# zoetrope.net
KiCad netlist of a schematic drawn in EAGLE
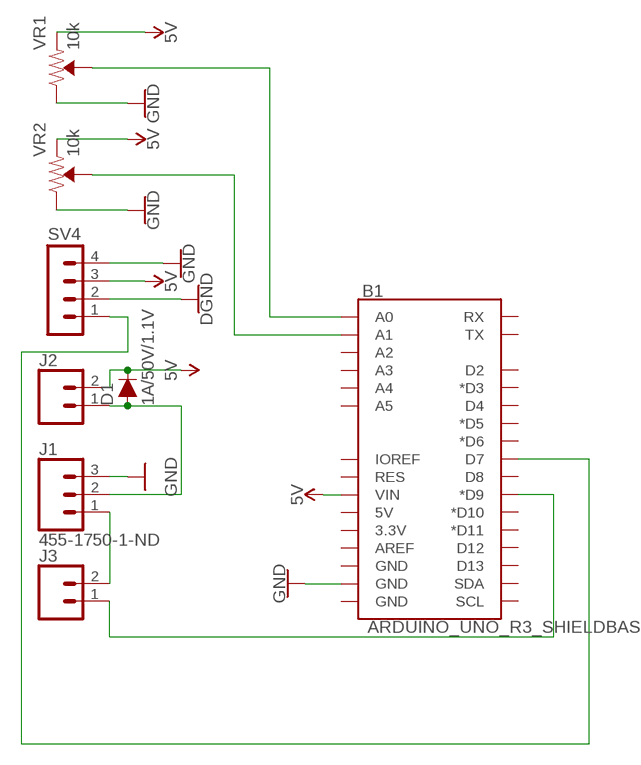
[diagram p0: schematic, sheet 1]

(export (version "E")
  (design (tool "Eeschema 10.0.6"))
  (components
    (comp (ref "B1")
      (value "ARDUINO_UNO_R3_SHIELDBASIC")
      (footprint "eagle-import:UNO_R3_SHIELD")
      (libsource (lib "eagle-import") (part "ARDUINO_UNO_R3_SHIELDBASIC"))
    )
    (comp (ref "D1")
      (value "1A/50V/1.1V")
      (footprint "eagle-import:DIODE-1N4001")
      (libsource (lib "eagle-import") (part "DIODE-PTH"))
    )
    (comp (ref "J1")
      (value "455-1750-1-ND")
      (footprint "eagle-import:1X03")
      (libsource (lib "eagle-import") (part "CONN_03"))
    )
    (comp (ref "J2")
      (value "CONN_02")
      (footprint "eagle-import:1X02")
      (libsource (lib "eagle-import") (part "CONN_02"))
    )
    (comp (ref "J3")
      (value "CONN_02")
      (footprint "eagle-import:1X02")
      (libsource (lib "eagle-import") (part "CONN_02"))
    )
    (comp (ref "SV4")
      (value "MA04-1")
      (footprint "eagle-import:MA04-1")
      (libsource (lib "eagle-import") (part "MA04-1"))
    )
    (comp (ref "VR1")
      (value "10k")
      (footprint "eagle-import:TRIMPOT-PTH-3386U")
      (libsource (lib "eagle-import") (part "TRIMPOT-PTH-10MM-KNOB-1/2W-10%"))
    )
    (comp (ref "VR2")
      (value "10k")
      (footprint "eagle-import:TRIMPOT-PTH-3386U")
      (libsource (lib "eagle-import") (part "TRIMPOT-PTH-10MM-KNOB-1/2W-10%"))
    )
  )
  (nets
    (net (code "1") (name "5V") (class "Default")
      (node (ref "B1") (pin "VIN") (pinfunction "VIN_VIN") (pintype "bidirectional"))
      (node (ref "D1") (pin "C") (pinfunction "C_C") (pintype "passive"))
      (node (ref "J2") (pin "2") (pinfunction "2_2") (pintype "passive"))
      (node (ref "SV4") (pin "3") (pinfunction "3_3") (pintype "passive"))
      (node (ref "VR1") (pin "1") (pinfunction "CCW_1") (pintype "passive"))
      (node (ref "VR2") (pin "1") (pinfunction "CCW_1") (pintype "passive"))
    )
    (net (code "2") (name "DGND") (class "Default")
      (node (ref "B1") (pin "GND@1") (pinfunction "GND_GND@1") (pintype "bidirectional"))
      (node (ref "J1") (pin "3") (pinfunction "3_3") (pintype "passive"))
      (node (ref "SV4") (pin "2") (pinfunction "2_2") (pintype "passive"))
      (node (ref "SV4") (pin "4") (pinfunction "4_4") (pintype "passive"))
      (node (ref "VR1") (pin "3") (pinfunction "CW_3") (pintype "passive"))
      (node (ref "VR2") (pin "3") (pinfunction "CW_3") (pintype "passive"))
    )
    (net (code "3") (name "Net-(B1-*D9)") (class "Default")
      (node (ref "B1") (pin "D9") (pinfunction "*D9_D9") (pintype "bidirectional"))
      (node (ref "J3") (pin "1") (pinfunction "1_1") (pintype "passive"))
    )
    (net (code "4") (name "Net-(B1-PadD7)") (class "Default")
      (node (ref "B1") (pin "D7") (pinfunction "D7_D7") (pintype "bidirectional"))
      (node (ref "SV4") (pin "1") (pinfunction "1_1") (pintype "passive"))
    )
    (net (code "5") (name "Net-(D1-PadA)") (class "Default")
      (node (ref "D1") (pin "A") (pinfunction "A_A") (pintype "passive"))
      (node (ref "J1") (pin "2") (pinfunction "2_2") (pintype "passive"))
      (node (ref "J2") (pin "1") (pinfunction "1_1") (pintype "passive"))
    )
    (net (code "6") (name "Net-(J1-Pad1)") (class "Default")
      (node (ref "J1") (pin "1") (pinfunction "1_1") (pintype "passive"))
      (node (ref "J3") (pin "2") (pinfunction "2_2") (pintype "passive"))
    )
    (net (code "7") (name "Net-(VR1-WIPER)") (class "Default")
      (node (ref "B1") (pin "A0") (pinfunction "A0_A0") (pintype "bidirectional"))
      (node (ref "VR1") (pin "2") (pinfunction "WIPER_2") (pintype "passive"))
    )
    (net (code "8") (name "Net-(VR2-WIPER)") (class "Default")
      (node (ref "B1") (pin "A1") (pinfunction "A1_A1") (pintype "bidirectional"))
      (node (ref "VR2") (pin "2") (pinfunction "WIPER_2") (pintype "passive"))
    )
    (net (code "9") (name "unconnected-(B1-*D3-PadD3)") (class "Default")
      (node (ref "B1") (pin "D3") (pinfunction "*D3_D3") (pintype "bidirectional"))
    )
    (net (code "10") (name "unconnected-(B1-*D5-PadD5)") (class "Default")
      (node (ref "B1") (pin "D5") (pinfunction "*D5_D5") (pintype "bidirectional"))
    )
    (net (code "11") (name "unconnected-(B1-*D6-PadD6)") (class "Default")
      (node (ref "B1") (pin "D6") (pinfunction "*D6_D6") (pintype "bidirectional"))
    )
    (net (code "12") (name "unconnected-(B1-*D10-PadD10)") (class "Default")
      (node (ref "B1") (pin "D10") (pinfunction "*D10_D10") (pintype "bidirectional"))
    )
    (net (code "13") (name "unconnected-(B1-*D11-PadD11)") (class "Default")
      (node (ref "B1") (pin "D11") (pinfunction "*D11_D11") (pintype "bidirectional"))
    )
    (net (code "14") (name "unconnected-(B1-GND-PadGND@0)") (class "Default")
      (node (ref "B1") (pin "GND@0") (pinfunction "GND_GND@0") (pintype "bidirectional"))
    )
    (net (code "15") (name "unconnected-(B1-GND-PadGND@2)") (class "Default")
      (node (ref "B1") (pin "GND@2") (pinfunction "GND_GND@2") (pintype "bidirectional"))
    )
    (net (code "16") (name "unconnected-(B1-Pad3.3V)") (class "Default")
      (node (ref "B1") (pin "3.3V") (pinfunction "3.3V_3.3V") (pintype "bidirectional"))
    )
    (net (code "17") (name "unconnected-(B1-Pad5V)") (class "Default")
      (node (ref "B1") (pin "5V") (pinfunction "5V_5V") (pintype "bidirectional"))
    )
    (net (code "18") (name "unconnected-(B1-PadA2)") (class "Default")
      (node (ref "B1") (pin "A2") (pinfunction "A2_A2") (pintype "bidirectional"))
    )
    (net (code "19") (name "unconnected-(B1-PadA3)") (class "Default")
      (node (ref "B1") (pin "A3") (pinfunction "A3_A3") (pintype "bidirectional"))
    )
    (net (code "20") (name "unconnected-(B1-PadA4)") (class "Default")
      (node (ref "B1") (pin "A4") (pinfunction "A4_A4") (pintype "bidirectional"))
    )
    (net (code "21") (name "unconnected-(B1-PadA5)") (class "Default")
      (node (ref "B1") (pin "A5") (pinfunction "A5_A5") (pintype "bidirectional"))
    )
    (net (code "22") (name "unconnected-(B1-PadAREF)") (class "Default")
      (node (ref "B1") (pin "AREF") (pinfunction "AREF_AREF") (pintype "bidirectional"))
    )
    (net (code "23") (name "unconnected-(B1-PadD2)") (class "Default")
      (node (ref "B1") (pin "D2") (pinfunction "D2_D2") (pintype "bidirectional"))
    )
    (net (code "24") (name "unconnected-(B1-PadD4)") (class "Default")
      (node (ref "B1") (pin "D4") (pinfunction "D4_D4") (pintype "bidirectional"))
    )
    (net (code "25") (name "unconnected-(B1-PadD8)") (class "Default")
      (node (ref "B1") (pin "D8") (pinfunction "D8_D8") (pintype "bidirectional"))
    )
    (net (code "26") (name "unconnected-(B1-PadD12)") (class "Default")
      (node (ref "B1") (pin "D12") (pinfunction "D12_D12") (pintype "bidirectional"))
    )
    (net (code "27") (name "unconnected-(B1-PadD13)") (class "Default")
      (node (ref "B1") (pin "D13") (pinfunction "D13_D13") (pintype "bidirectional"))
    )
    (net (code "28") (name "unconnected-(B1-PadIOREF)") (class "Default")
      (node (ref "B1") (pin "IOREF") (pinfunction "IOREF_IOREF") (pintype "bidirectional"))
    )
    (net (code "29") (name "unconnected-(B1-PadRES)") (class "Default")
      (node (ref "B1") (pin "RES") (pinfunction "RES_RES") (pintype "bidirectional"))
    )
    (net (code "30") (name "unconnected-(B1-PadRX)") (class "Default")
      (node (ref "B1") (pin "RX") (pinfunction "RX_RX") (pintype "bidirectional"))
    )
    (net (code "31") (name "unconnected-(B1-PadSCL)") (class "Default")
      (node (ref "B1") (pin "SCL") (pinfunction "SCL_SCL") (pintype "bidirectional"))
    )
    (net (code "32") (name "unconnected-(B1-PadSDA)") (class "Default")
      (node (ref "B1") (pin "SDA") (pinfunction "SDA_SDA") (pintype "bidirectional"))
    )
    (net (code "33") (name "unconnected-(B1-PadTX)") (class "Default")
      (node (ref "B1") (pin "TX") (pinfunction "TX_TX") (pintype "bidirectional"))
    )
  )
)
